# Philharmonic12.net
KiCad netlist of a schematic drawn in EAGLE
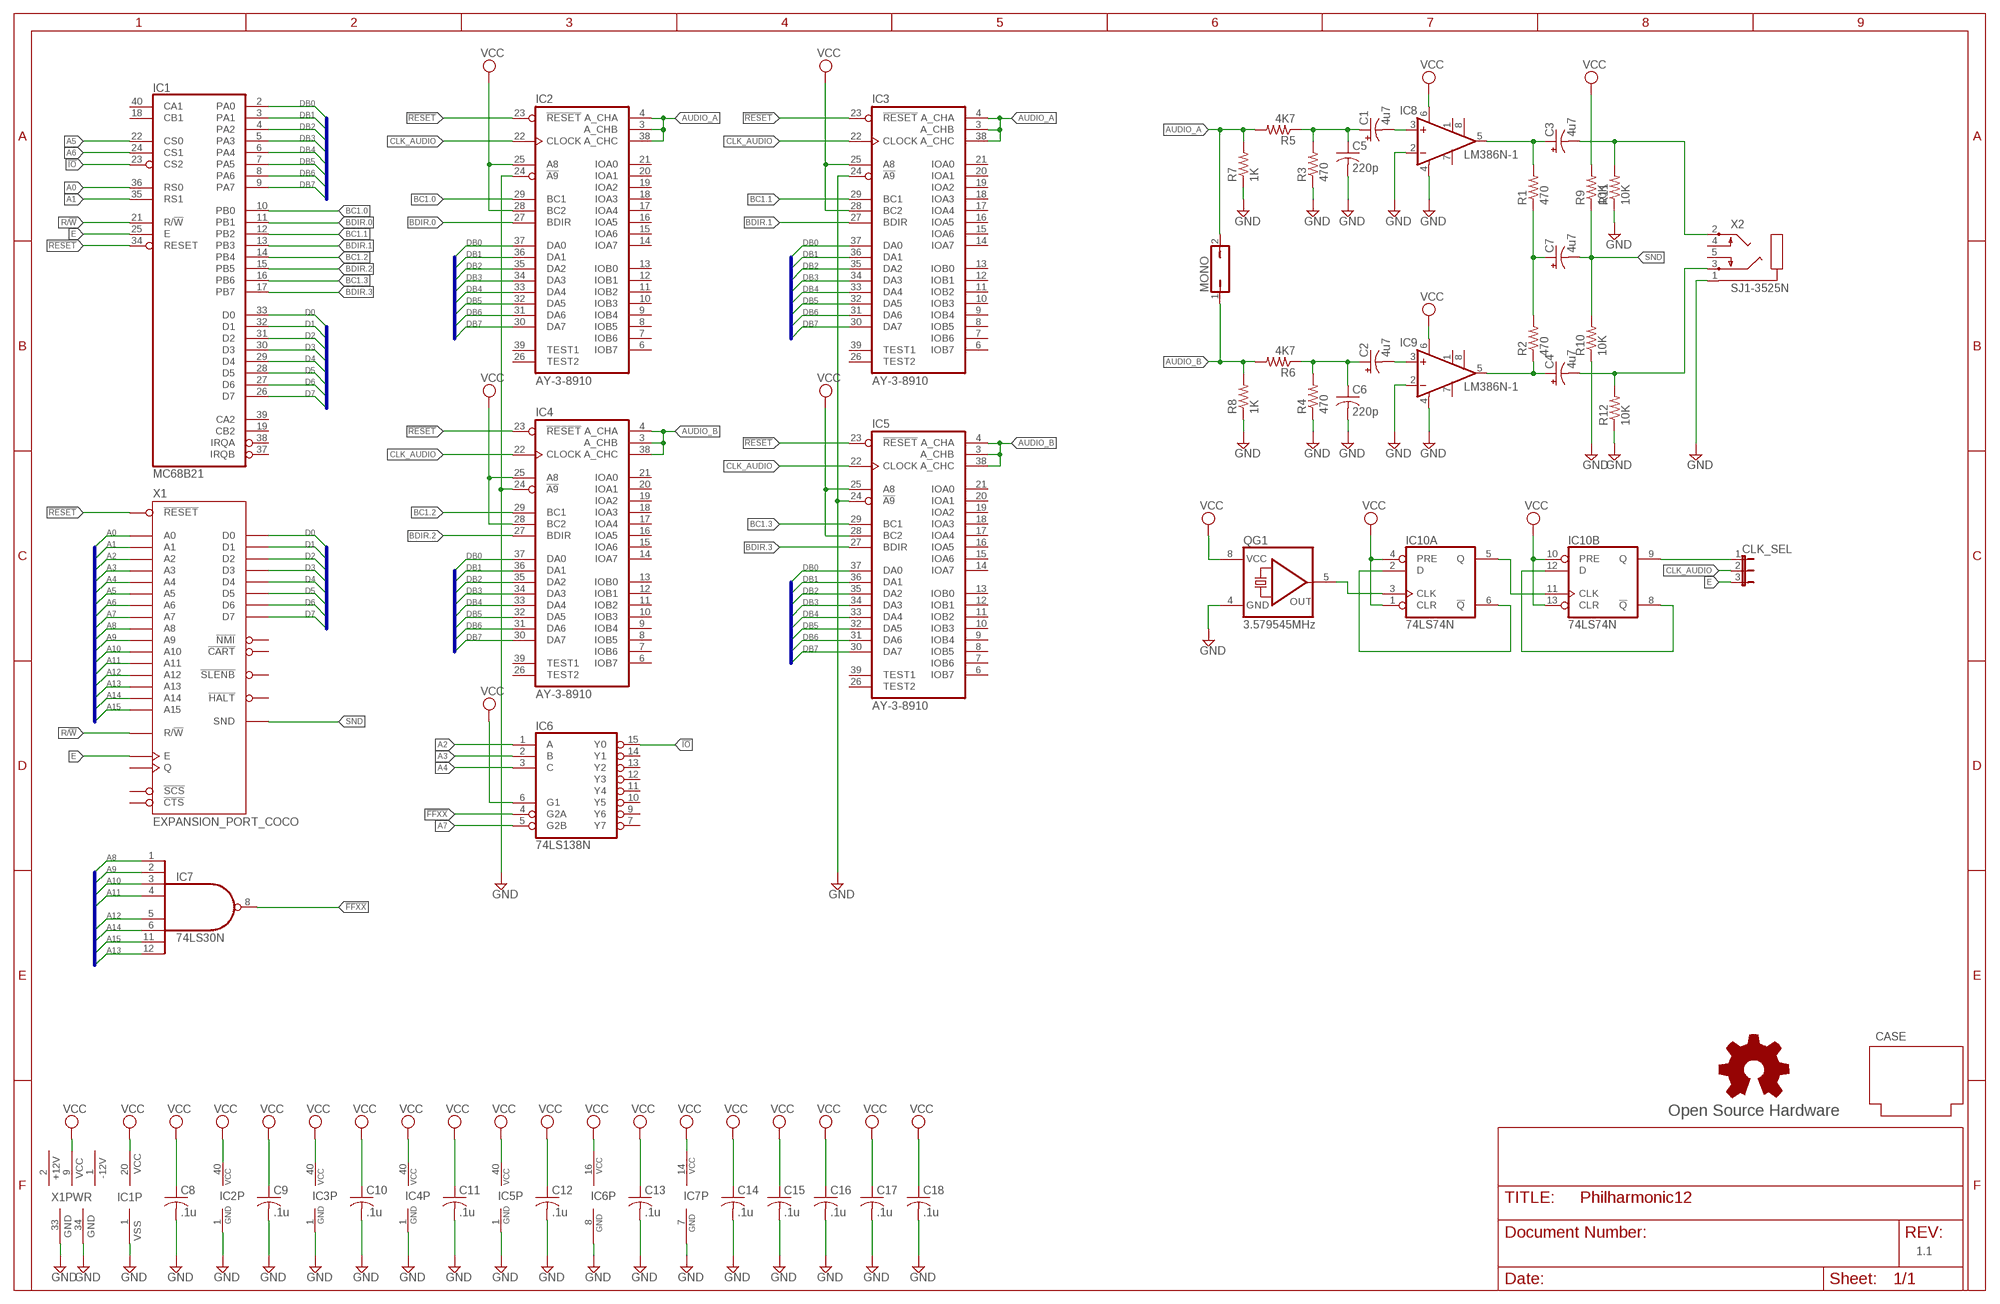
[diagram p0: schematic, sheet 1]

(export (version "E")
  (design (tool "Eeschema 10.0.6"))
  (components
    (comp (ref "C1")
      (value "4u7")
      (footprint "eagle-import:E2,5-6")
      (libsource (lib "eagle-import") (part "CPOL-USE2.5-6"))
    )
    (comp (ref "C2")
      (value "4u7")
      (footprint "eagle-import:E2,5-6")
      (libsource (lib "eagle-import") (part "CPOL-USE2.5-6"))
    )
    (comp (ref "C3")
      (value "4u7")
      (footprint "eagle-import:E2,5-6")
      (libsource (lib "eagle-import") (part "CPOL-USE2.5-6"))
    )
    (comp (ref "C4")
      (value "4u7")
      (footprint "eagle-import:E2,5-6")
      (libsource (lib "eagle-import") (part "CPOL-USE2.5-6"))
    )
    (comp (ref "C5")
      (value "220p")
      (footprint "eagle-import:C025-025X050")
      (libsource (lib "eagle-import") (part "C-US025-025X050"))
    )
    (comp (ref "C6")
      (value "220p")
      (footprint "eagle-import:C025-025X050")
      (libsource (lib "eagle-import") (part "C-US025-025X050"))
    )
    (comp (ref "C7")
      (value "4u7")
      (footprint "eagle-import:E2,5-6")
      (libsource (lib "eagle-import") (part "CPOL-USE2.5-6"))
    )
    (comp (ref "C8")
      (value ".1u")
      (footprint "eagle-import:C025-025X050")
      (libsource (lib "eagle-import") (part "C-US025-025X050"))
    )
    (comp (ref "C9")
      (value ".1u")
      (footprint "eagle-import:C025-025X050")
      (libsource (lib "eagle-import") (part "C-US025-025X050"))
    )
    (comp (ref "C10")
      (value ".1u")
      (footprint "eagle-import:C025-025X050")
      (libsource (lib "eagle-import") (part "C-US025-025X050"))
    )
    (comp (ref "C11")
      (value ".1u")
      (footprint "eagle-import:C025-025X050")
      (libsource (lib "eagle-import") (part "C-US025-025X050"))
    )
    (comp (ref "C12")
      (value ".1u")
      (footprint "eagle-import:C025-025X050")
      (libsource (lib "eagle-import") (part "C-US025-025X050"))
    )
    (comp (ref "C13")
      (value ".1u")
      (footprint "eagle-import:C025-025X050")
      (libsource (lib "eagle-import") (part "C-US025-025X050"))
    )
    (comp (ref "C14")
      (value ".1u")
      (footprint "eagle-import:C025-025X050")
      (libsource (lib "eagle-import") (part "C-US025-025X050"))
    )
    (comp (ref "C15")
      (value ".1u")
      (footprint "eagle-import:C025-025X050")
      (libsource (lib "eagle-import") (part "C-US025-025X050"))
    )
    (comp (ref "C16")
      (value ".1u")
      (footprint "eagle-import:C025-025X050")
      (libsource (lib "eagle-import") (part "C-US025-025X050"))
    )
    (comp (ref "C17")
      (value ".1u")
      (footprint "eagle-import:C025-025X050")
      (libsource (lib "eagle-import") (part "C-US025-025X050"))
    )
    (comp (ref "C18")
      (value ".1u")
      (footprint "eagle-import:C025-025X050")
      (libsource (lib "eagle-import") (part "C-US025-025X050"))
    )
    (comp (ref "CASE")
      (value "PROGRAM_PAK")
      (footprint "eagle-import:PROGRAM_PAK")
      (libsource (lib "eagle-import") (part "PROGRAM_PAK"))
    )
    (comp (ref "CLK_SEL")
      (value "JP2E")
      (footprint "eagle-import:JP2")
      (libsource (lib "eagle-import") (part "JP2E"))
    )
    (comp (ref "GOLD_ORB_SM1")
      (value "Open Source Hardware")
      (footprint "eagle-import:OSHW_5MM")
      (libsource (lib "eagle-import") (part "OSHWLOGOLOGO5MM"))
    )
    (comp (ref "IC1")
      (value "MC68B21")
      (footprint "eagle-import:DIL40-ROUNDPAD")
      (libsource (lib "eagle-import") (part "6821R"))
    )
    (comp (ref "IC2")
      (value "AY-3-8910")
      (footprint "eagle-import:DIL40-RP")
      (libsource (lib "eagle-import") (part "AY-3-8910-RP"))
    )
    (comp (ref "IC3")
      (value "AY-3-8910")
      (footprint "eagle-import:DIL40-RP")
      (libsource (lib "eagle-import") (part "AY-3-8910-RP"))
    )
    (comp (ref "IC4")
      (value "AY-3-8910")
      (footprint "eagle-import:DIL40-RP")
      (libsource (lib "eagle-import") (part "AY-3-8910-RP"))
    )
    (comp (ref "IC5")
      (value "AY-3-8910")
      (footprint "eagle-import:DIL40-RP")
      (libsource (lib "eagle-import") (part "AY-3-8910-RP"))
    )
    (comp (ref "IC6")
      (value "74LS138N")
      (footprint "eagle-import:DIL16-RP")
      (libsource (lib "eagle-import") (part "74138NLS"))
    )
    (comp (ref "IC7")
      (value "74LS30N")
      (footprint "eagle-import:DIL14-RP")
      (libsource (lib "eagle-import") (part "7430NALS"))
    )
    (comp (ref "IC8")
      (value "LM386N-1")
      (footprint "eagle-import:DIL08")
      (libsource (lib "eagle-import") (part "LM386?-N1"))
    )
    (comp (ref "IC9")
      (value "LM386N-1")
      (footprint "eagle-import:DIL08")
      (libsource (lib "eagle-import") (part "LM386?-N1"))
    )
    (comp (ref "IC10")
      (value "74LS74N")
      (footprint "eagle-import:DIL14-RP")
      (libsource (lib "eagle-import") (part "7474NLS"))
    )
    (comp (ref "MONO")
      (value "JP1Q")
      (footprint "eagle-import:JP1")
      (libsource (lib "eagle-import") (part "JP1Q"))
    )
    (comp (ref "QG1")
      (value "3.579545MHz")
      (footprint "eagle-import:DIL08S")
      (libsource (lib "eagle-import") (part "QG5460"))
    )
    (comp (ref "R1")
      (value "470")
      (footprint "eagle-import:0204_7")
      (libsource (lib "eagle-import") (part "R-US_0204/7"))
    )
    (comp (ref "R2")
      (value "470")
      (footprint "eagle-import:0204_7")
      (libsource (lib "eagle-import") (part "R-US_0204/7"))
    )
    (comp (ref "R3")
      (value "470")
      (footprint "eagle-import:0204_7")
      (libsource (lib "eagle-import") (part "R-US_0204/7"))
    )
    (comp (ref "R4")
      (value "470")
      (footprint "eagle-import:0204_7")
      (libsource (lib "eagle-import") (part "R-US_0204/7"))
    )
    (comp (ref "R5")
      (value "4K7")
      (footprint "eagle-import:0204_7")
      (libsource (lib "eagle-import") (part "R-US_0204/7"))
    )
    (comp (ref "R6")
      (value "4K7")
      (footprint "eagle-import:0204_7")
      (libsource (lib "eagle-import") (part "R-US_0204/7"))
    )
    (comp (ref "R7")
      (value "1K")
      (footprint "eagle-import:0204_7")
      (libsource (lib "eagle-import") (part "R-US_0204/7"))
    )
    (comp (ref "R8")
      (value "1K")
      (footprint "eagle-import:0204_7")
      (libsource (lib "eagle-import") (part "R-US_0204/7"))
    )
    (comp (ref "R9")
      (value "10K")
      (footprint "eagle-import:0204_7")
      (libsource (lib "eagle-import") (part "R-US_0204/7"))
    )
    (comp (ref "R10")
      (value "10K")
      (footprint "eagle-import:0204_7")
      (libsource (lib "eagle-import") (part "R-US_0204/7"))
    )
    (comp (ref "R11")
      (value "10K")
      (footprint "eagle-import:0204_7")
      (libsource (lib "eagle-import") (part "R-US_0204/7"))
    )
    (comp (ref "R12")
      (value "10K")
      (footprint "eagle-import:0204_7")
      (libsource (lib "eagle-import") (part "R-US_0204/7"))
    )
    (comp (ref "X1")
      (value "EXPANSION_PORT_COCO")
      (footprint "eagle-import:MA20-2")
      (libsource (lib "eagle-import") (part "EXPANSION_PORT_COCO"))
    )
    (comp (ref "X2")
      (value "SJ1-3525N")
      (footprint "eagle-import:SJ1-3525N")
      (libsource (lib "eagle-import") (part "SJ1-3525N"))
    )
  )
  (nets
    (net (code "1") (name "/+12V") (class "Default")
      (node (ref "X1") (pin "2") (pinfunction "+12V_2") (pintype "power_in"))
    )
    (net (code "2") (name "/-12V") (class "Default")
      (node (ref "X1") (pin "1") (pinfunction "-12V_1") (pintype "power_in"))
    )
    (net (code "3") (name "/A8") (class "Default")
      (node (ref "IC7") (pin "1") (pinfunction "I0_1") (pintype "input"))
      (node (ref "X1") (pin "27") (pinfunction "A8_27") (pintype "output"))
    )
    (net (code "4") (name "/A9") (class "Default")
      (node (ref "IC7") (pin "2") (pinfunction "I1_2") (pintype "input"))
      (node (ref "X1") (pin "28") (pinfunction "A9_28") (pintype "output"))
    )
    (net (code "5") (name "/A10") (class "Default")
      (node (ref "IC7") (pin "3") (pinfunction "I2_3") (pintype "input"))
      (node (ref "X1") (pin "29") (pinfunction "A10_29") (pintype "output"))
    )
    (net (code "6") (name "/A11") (class "Default")
      (node (ref "IC7") (pin "4") (pinfunction "I3_4") (pintype "input"))
      (node (ref "X1") (pin "30") (pinfunction "A11_30") (pintype "output"))
    )
    (net (code "7") (name "/A12") (class "Default")
      (node (ref "IC7") (pin "5") (pinfunction "I4_5") (pintype "input"))
      (node (ref "X1") (pin "31") (pinfunction "A12_31") (pintype "output"))
    )
    (net (code "8") (name "/A13") (class "Default")
      (node (ref "IC7") (pin "12") (pinfunction "I7_12") (pintype "input"))
      (node (ref "X1") (pin "37") (pinfunction "A13_37") (pintype "output"))
    )
    (net (code "9") (name "/A14") (class "Default")
      (node (ref "IC7") (pin "6") (pinfunction "I5_6") (pintype "input"))
      (node (ref "X1") (pin "38") (pinfunction "A14_38") (pintype "output"))
    )
    (net (code "10") (name "/A15") (class "Default")
      (node (ref "IC7") (pin "11") (pinfunction "I6_11") (pintype "input"))
      (node (ref "X1") (pin "39") (pinfunction "A15_39") (pintype "output"))
    )
    (net (code "11") (name "/D0") (class "Default")
      (node (ref "IC1") (pin "33") (pinfunction "D0_33") (pintype "bidirectional"))
      (node (ref "X1") (pin "10") (pinfunction "D0_10") (pintype "bidirectional"))
    )
    (net (code "12") (name "/D1") (class "Default")
      (node (ref "IC1") (pin "32") (pinfunction "D1_32") (pintype "bidirectional"))
      (node (ref "X1") (pin "11") (pinfunction "D1_11") (pintype "bidirectional"))
    )
    (net (code "13") (name "/D2") (class "Default")
      (node (ref "IC1") (pin "31") (pinfunction "D2_31") (pintype "bidirectional"))
      (node (ref "X1") (pin "12") (pinfunction "D2_12") (pintype "bidirectional"))
    )
    (net (code "14") (name "/D3") (class "Default")
      (node (ref "IC1") (pin "30") (pinfunction "D3_30") (pintype "bidirectional"))
      (node (ref "X1") (pin "13") (pinfunction "D3_13") (pintype "bidirectional"))
    )
    (net (code "15") (name "/D4") (class "Default")
      (node (ref "IC1") (pin "29") (pinfunction "D4_29") (pintype "bidirectional"))
      (node (ref "X1") (pin "14") (pinfunction "D4_14") (pintype "bidirectional"))
    )
    (net (code "16") (name "/D5") (class "Default")
      (node (ref "IC1") (pin "28") (pinfunction "D5_28") (pintype "bidirectional"))
      (node (ref "X1") (pin "15") (pinfunction "D5_15") (pintype "bidirectional"))
    )
    (net (code "17") (name "/D6") (class "Default")
      (node (ref "IC1") (pin "27") (pinfunction "D6_27") (pintype "bidirectional"))
      (node (ref "X1") (pin "16") (pinfunction "D6_16") (pintype "bidirectional"))
    )
    (net (code "18") (name "/D7") (class "Default")
      (node (ref "IC1") (pin "26") (pinfunction "D7_26") (pintype "bidirectional"))
      (node (ref "X1") (pin "17") (pinfunction "D7_17") (pintype "bidirectional"))
    )
    (net (code "19") (name "/DB0") (class "Default")
      (node (ref "IC1") (pin "2") (pinfunction "PA0_2") (pintype "bidirectional"))
      (node (ref "IC2") (pin "37") (pinfunction "DA0_37") (pintype "bidirectional"))
      (node (ref "IC3") (pin "37") (pinfunction "DA0_37") (pintype "bidirectional"))
      (node (ref "IC4") (pin "37") (pinfunction "DA0_37") (pintype "bidirectional"))
      (node (ref "IC5") (pin "37") (pinfunction "DA0_37") (pintype "bidirectional"))
    )
    (net (code "20") (name "/DB1") (class "Default")
      (node (ref "IC1") (pin "3") (pinfunction "PA1_3") (pintype "bidirectional"))
      (node (ref "IC2") (pin "36") (pinfunction "DA1_36") (pintype "bidirectional"))
      (node (ref "IC3") (pin "36") (pinfunction "DA1_36") (pintype "bidirectional"))
      (node (ref "IC4") (pin "36") (pinfunction "DA1_36") (pintype "bidirectional"))
      (node (ref "IC5") (pin "36") (pinfunction "DA1_36") (pintype "bidirectional"))
    )
    (net (code "21") (name "/DB2") (class "Default")
      (node (ref "IC1") (pin "4") (pinfunction "PA2_4") (pintype "bidirectional"))
      (node (ref "IC2") (pin "35") (pinfunction "DA2_35") (pintype "bidirectional"))
      (node (ref "IC3") (pin "35") (pinfunction "DA2_35") (pintype "bidirectional"))
      (node (ref "IC4") (pin "35") (pinfunction "DA2_35") (pintype "bidirectional"))
      (node (ref "IC5") (pin "35") (pinfunction "DA2_35") (pintype "bidirectional"))
    )
    (net (code "22") (name "/DB3") (class "Default")
      (node (ref "IC1") (pin "5") (pinfunction "PA3_5") (pintype "bidirectional"))
      (node (ref "IC2") (pin "34") (pinfunction "DA3_34") (pintype "bidirectional"))
      (node (ref "IC3") (pin "34") (pinfunction "DA3_34") (pintype "bidirectional"))
      (node (ref "IC4") (pin "34") (pinfunction "DA3_34") (pintype "bidirectional"))
      (node (ref "IC5") (pin "34") (pinfunction "DA3_34") (pintype "bidirectional"))
    )
    (net (code "23") (name "/DB4") (class "Default")
      (node (ref "IC1") (pin "6") (pinfunction "PA4_6") (pintype "bidirectional"))
      (node (ref "IC2") (pin "33") (pinfunction "DA4_33") (pintype "bidirectional"))
      (node (ref "IC3") (pin "33") (pinfunction "DA4_33") (pintype "bidirectional"))
      (node (ref "IC4") (pin "33") (pinfunction "DA4_33") (pintype "bidirectional"))
      (node (ref "IC5") (pin "33") (pinfunction "DA4_33") (pintype "bidirectional"))
    )
    (net (code "24") (name "/DB5") (class "Default")
      (node (ref "IC1") (pin "7") (pinfunction "PA5_7") (pintype "bidirectional"))
      (node (ref "IC2") (pin "32") (pinfunction "DA5_32") (pintype "bidirectional"))
      (node (ref "IC3") (pin "32") (pinfunction "DA5_32") (pintype "bidirectional"))
      (node (ref "IC4") (pin "32") (pinfunction "DA5_32") (pintype "bidirectional"))
      (node (ref "IC5") (pin "32") (pinfunction "DA5_32") (pintype "bidirectional"))
    )
    (net (code "25") (name "/DB6") (class "Default")
      (node (ref "IC1") (pin "8") (pinfunction "PA6_8") (pintype "bidirectional"))
      (node (ref "IC2") (pin "31") (pinfunction "DA6_31") (pintype "bidirectional"))
      (node (ref "IC3") (pin "31") (pinfunction "DA6_31") (pintype "bidirectional"))
      (node (ref "IC4") (pin "31") (pinfunction "DA6_31") (pintype "bidirectional"))
      (node (ref "IC5") (pin "31") (pinfunction "DA6_31") (pintype "bidirectional"))
    )
    (net (code "26") (name "/DB7") (class "Default")
      (node (ref "IC1") (pin "9") (pinfunction "PA7_9") (pintype "bidirectional"))
      (node (ref "IC2") (pin "30") (pinfunction "DA7_30") (pintype "bidirectional"))
      (node (ref "IC3") (pin "30") (pinfunction "DA7_30") (pintype "bidirectional"))
      (node (ref "IC4") (pin "30") (pinfunction "DA7_30") (pintype "bidirectional"))
      (node (ref "IC5") (pin "30") (pinfunction "DA7_30") (pintype "bidirectional"))
    )
    (net (code "27") (name "/R{slash}~{W}") (class "Default")
      (node (ref "IC1") (pin "21") (pinfunction "R/~{W}_21") (pintype "input"))
      (node (ref "X1") (pin "18") (pinfunction "R/~{W}_18") (pintype "output"))
    )
    (net (code "28") (name "/~{FFXX}") (class "Default")
      (node (ref "IC6") (pin "4") (pinfunction "G2A_4") (pintype "input"))
      (node (ref "IC7") (pin "8") (pinfunction "O_8") (pintype "output"))
    )
    (net (code "29") (name "/~{IO}") (class "Default")
      (node (ref "IC1") (pin "23") (pinfunction "CS2_23") (pintype "input"))
      (node (ref "IC6") (pin "15") (pinfunction "Y0_15") (pintype "output"))
    )
    (net (code "30") (name "/~{RESET}") (class "Default")
      (node (ref "IC1") (pin "34") (pinfunction "RESET_34") (pintype "input"))
      (node (ref "IC2") (pin "23") (pinfunction "~{RESET}_23") (pintype "input"))
      (node (ref "IC3") (pin "23") (pinfunction "~{RESET}_23") (pintype "input"))
      (node (ref "IC4") (pin "23") (pinfunction "~{RESET}_23") (pintype "input"))
      (node (ref "IC5") (pin "23") (pinfunction "~{RESET}_23") (pintype "input"))
      (node (ref "X1") (pin "5") (pinfunction "~{RESET}_5") (pintype "open_collector"))
    )
    (net (code "31") (name "A0") (class "Default")
      (node (ref "IC1") (pin "36") (pinfunction "RS0_36") (pintype "input"))
      (node (ref "X1") (pin "19") (pinfunction "A0_19") (pintype "output"))
    )
    (net (code "32") (name "A1") (class "Default")
      (node (ref "IC1") (pin "35") (pinfunction "RS1_35") (pintype "input"))
      (node (ref "X1") (pin "20") (pinfunction "A1_20") (pintype "output"))
    )
    (net (code "33") (name "A2") (class "Default")
      (node (ref "IC6") (pin "1") (pinfunction "A_1") (pintype "input"))
      (node (ref "X1") (pin "21") (pinfunction "A2_21") (pintype "output"))
    )
    (net (code "34") (name "A3") (class "Default")
      (node (ref "IC6") (pin "2") (pinfunction "B_2") (pintype "input"))
      (node (ref "X1") (pin "22") (pinfunction "A3_22") (pintype "output"))
    )
    (net (code "35") (name "A4") (class "Default")
      (node (ref "IC6") (pin "3") (pinfunction "C_3") (pintype "input"))
      (node (ref "X1") (pin "23") (pinfunction "A4_23") (pintype "output"))
    )
    (net (code "36") (name "A5") (class "Default")
      (node (ref "IC1") (pin "22") (pinfunction "CS0_22") (pintype "input"))
      (node (ref "X1") (pin "24") (pinfunction "A5_24") (pintype "output"))
    )
    (net (code "37") (name "A6") (class "Default")
      (node (ref "IC1") (pin "24") (pinfunction "CS1_24") (pintype "input"))
      (node (ref "X1") (pin "25") (pinfunction "A6_25") (pintype "output"))
    )
    (net (code "38") (name "A7") (class "Default")
      (node (ref "IC6") (pin "5") (pinfunction "G2B_5") (pintype "input"))
      (node (ref "X1") (pin "26") (pinfunction "A7_26") (pintype "output"))
    )
    (net (code "39") (name "AUDIO_A") (class "Default")
      (node (ref "IC2") (pin "3") (pinfunction "A_CHB_3") (pintype "output"))
      (node (ref "IC2") (pin "38") (pinfunction "A_CHC_38") (pintype "output"))
      (node (ref "IC2") (pin "4") (pinfunction "A_CHA_4") (pintype "output"))
      (node (ref "IC3") (pin "3") (pinfunction "A_CHB_3") (pintype "output"))
      (node (ref "IC3") (pin "38") (pinfunction "A_CHC_38") (pintype "output"))
      (node (ref "IC3") (pin "4") (pinfunction "A_CHA_4") (pintype "output"))
      (node (ref "MONO") (pin "2") (pinfunction "2_2") (pintype "passive"))
      (node (ref "R5") (pin "2") (pinfunction "2_2") (pintype "passive"))
      (node (ref "R7") (pin "2") (pinfunction "2_2") (pintype "passive"))
    )
    (net (code "40") (name "AUDIO_B") (class "Default")
      (node (ref "IC4") (pin "3") (pinfunction "A_CHB_3") (pintype "output"))
      (node (ref "IC4") (pin "38") (pinfunction "A_CHC_38") (pintype "output"))
      (node (ref "IC4") (pin "4") (pinfunction "A_CHA_4") (pintype "output"))
      (node (ref "IC5") (pin "3") (pinfunction "A_CHB_3") (pintype "output"))
      (node (ref "IC5") (pin "38") (pinfunction "A_CHC_38") (pintype "output"))
      (node (ref "IC5") (pin "4") (pinfunction "A_CHA_4") (pintype "output"))
      (node (ref "MONO") (pin "1") (pinfunction "1_1") (pintype "passive"))
      (node (ref "R6") (pin "2") (pinfunction "2_2") (pintype "passive"))
      (node (ref "R8") (pin "2") (pinfunction "2_2") (pintype "passive"))
    )
    (net (code "41") (name "BC1.0") (class "Default")
      (node (ref "IC1") (pin "10") (pinfunction "PB0_10") (pintype "bidirectional"))
      (node (ref "IC2") (pin "29") (pinfunction "BC1_29") (pintype "input"))
    )
    (net (code "42") (name "BC1.1") (class "Default")
      (node (ref "IC1") (pin "12") (pinfunction "PB2_12") (pintype "bidirectional"))
      (node (ref "IC3") (pin "29") (pinfunction "BC1_29") (pintype "input"))
    )
    (net (code "43") (name "BC1.2") (class "Default")
      (node (ref "IC1") (pin "14") (pinfunction "PB4_14") (pintype "bidirectional"))
      (node (ref "IC4") (pin "29") (pinfunction "BC1_29") (pintype "input"))
    )
    (net (code "44") (name "BC1.3") (class "Default")
      (node (ref "IC1") (pin "16") (pinfunction "PB6_16") (pintype "bidirectional"))
      (node (ref "IC5") (pin "29") (pinfunction "BC1_29") (pintype "input"))
    )
    (net (code "45") (name "BDIR.0") (class "Default")
      (node (ref "IC1") (pin "11") (pinfunction "PB1_11") (pintype "bidirectional"))
      (node (ref "IC2") (pin "27") (pinfunction "BDIR_27") (pintype "input"))
    )
    (net (code "46") (name "BDIR.1") (class "Default")
      (node (ref "IC1") (pin "13") (pinfunction "PB3_13") (pintype "bidirectional"))
      (node (ref "IC3") (pin "27") (pinfunction "BDIR_27") (pintype "input"))
    )
    (net (code "47") (name "BDIR.2") (class "Default")
      (node (ref "IC1") (pin "15") (pinfunction "PB5_15") (pintype "bidirectional"))
      (node (ref "IC4") (pin "27") (pinfunction "BDIR_27") (pintype "input"))
    )
    (net (code "48") (name "BDIR.3") (class "Default")
      (node (ref "IC1") (pin "17") (pinfunction "PB7_17") (pintype "bidirectional"))
      (node (ref "IC5") (pin "27") (pinfunction "BDIR_27") (pintype "input"))
    )
    (net (code "49") (name "CLK_AUDIO") (class "Default")
      (node (ref "CLK_SEL") (pin "2") (pinfunction "2_2") (pintype "passive"))
      (node (ref "IC2") (pin "22") (pinfunction "CLOCK_22") (pintype "input"))
      (node (ref "IC3") (pin "22") (pinfunction "CLOCK_22") (pintype "input"))
      (node (ref "IC4") (pin "22") (pinfunction "CLOCK_22") (pintype "input"))
      (node (ref "IC5") (pin "22") (pinfunction "CLOCK_22") (pintype "input"))
    )
    (net (code "50") (name "E") (class "Default")
      (node (ref "CLK_SEL") (pin "3") (pinfunction "3_3") (pintype "passive"))
      (node (ref "IC1") (pin "25") (pinfunction "E_25") (pintype "input"))
      (node (ref "X1") (pin "6") (pinfunction "E_6") (pintype "output"))
    )
    (net (code "51") (name "GND") (class "Default")
      (node (ref "C10") (pin "2") (pinfunction "2_2") (pintype "passive"))
      (node (ref "C11") (pin "2") (pinfunction "2_2") (pintype "passive"))
      (node (ref "C12") (pin "2") (pinfunction "2_2") (pintype "passive"))
      (node (ref "C13") (pin "2") (pinfunction "2_2") (pintype "passive"))
      (node (ref "C14") (pin "2") (pinfunction "2_2") (pintype "passive"))
      (node (ref "C15") (pin "2") (pinfunction "2_2") (pintype "passive"))
      (node (ref "C16") (pin "2") (pinfunction "2_2") (pintype "passive"))
      (node (ref "C17") (pin "2") (pinfunction "2_2") (pintype "passive"))
      (node (ref "C18") (pin "2") (pinfunction "2_2") (pintype "passive"))
      (node (ref "C5") (pin "2") (pinfunction "2_2") (pintype "passive"))
      (node (ref "C6") (pin "2") (pinfunction "2_2") (pintype "passive"))
      (node (ref "C8") (pin "2") (pinfunction "2_2") (pintype "passive"))
      (node (ref "C9") (pin "2") (pinfunction "2_2") (pintype "passive"))
      (node (ref "IC1") (pin "1") (pinfunction "VSS_1") (pintype "power_in"))
      (node (ref "IC2") (pin "1") (pinfunction "GND_1") (pintype "power_in"))
      (node (ref "IC2") (pin "24") (pinfunction "~{A9}_24") (pintype "input"))
      (node (ref "IC3") (pin "1") (pinfunction "GND_1") (pintype "power_in"))
      (node (ref "IC3") (pin "24") (pinfunction "~{A9}_24") (pintype "input"))
      (node (ref "IC4") (pin "1") (pinfunction "GND_1") (pintype "power_in"))
      (node (ref "IC4") (pin "24") (pinfunction "~{A9}_24") (pintype "input"))
      (node (ref "IC5") (pin "1") (pinfunction "GND_1") (pintype "power_in"))
      (node (ref "IC5") (pin "24") (pinfunction "~{A9}_24") (pintype "input"))
      (node (ref "IC6") (pin "8") (pinfunction "GND_8") (pintype "power_in"))
      (node (ref "IC7") (pin "7") (pinfunction "GND_7") (pintype "power_in"))
      (node (ref "IC8") (pin "2") (pinfunction "-IN_2") (pintype "input"))
      (node (ref "IC8") (pin "4") (pinfunction "GND_4") (pintype "power_in"))
      (node (ref "IC9") (pin "2") (pinfunction "-IN_2") (pintype "input"))
      (node (ref "IC9") (pin "4") (pinfunction "GND_4") (pintype "power_in"))
      (node (ref "QG1") (pin "4") (pinfunction "GND_4") (pintype "power_in"))
      (node (ref "R10") (pin "1") (pinfunction "1_1") (pintype "passive"))
      (node (ref "R11") (pin "1") (pinfunction "1_1") (pintype "passive"))
      (node (ref "R12") (pin "1") (pinfunction "1_1") (pintype "passive"))
      (node (ref "R3") (pin "1") (pinfunction "1_1") (pintype "passive"))
      (node (ref "R4") (pin "1") (pinfunction "1_1") (pintype "passive"))
      (node (ref "R7") (pin "1") (pinfunction "1_1") (pintype "passive"))
      (node (ref "R8") (pin "1") (pinfunction "1_1") (pintype "passive"))
      (node (ref "X1") (pin "33") (pinfunction "GND_33") (pintype "power_in"))
      (node (ref "X1") (pin "34") (pinfunction "GND_34") (pintype "power_in"))
      (node (ref "X2") (pin "1") (pinfunction "1_1") (pintype "passive"))
    )
    (net (code "52") (name "Net-(C1-Pad+)") (class "Default")
      (node (ref "C1") (pin "+") (pinfunction "+_+") (pintype "passive"))
      (node (ref "C5") (pin "1") (pinfunction "1_1") (pintype "passive"))
      (node (ref "R3") (pin "2") (pinfunction "2_2") (pintype "passive"))
      (node (ref "R5") (pin "1") (pinfunction "1_1") (pintype "passive"))
    )
    (net (code "53") (name "Net-(C2-Pad+)") (class "Default")
      (node (ref "C2") (pin "+") (pinfunction "+_+") (pintype "passive"))
      (node (ref "C6") (pin "1") (pinfunction "1_1") (pintype "passive"))
      (node (ref "R4") (pin "2") (pinfunction "2_2") (pintype "passive"))
      (node (ref "R6") (pin "1") (pinfunction "1_1") (pintype "passive"))
    )
    (net (code "54") (name "Net-(C3-Pad-)") (class "Default")
      (node (ref "C3") (pin "-") (pinfunction "-_-") (pintype "passive"))
      (node (ref "R11") (pin "2") (pinfunction "2_2") (pintype "passive"))
      (node (ref "X2") (pin "2") (pinfunction "2_2") (pintype "passive"))
    )
    (net (code "55") (name "Net-(C4-Pad-)") (class "Default")
      (node (ref "C4") (pin "-") (pinfunction "-_-") (pintype "passive"))
      (node (ref "R12") (pin "2") (pinfunction "2_2") (pintype "passive"))
      (node (ref "X2") (pin "3") (pinfunction "3_3") (pintype "passive"))
    )
    (net (code "56") (name "Net-(C7-Pad+)") (class "Default")
      (node (ref "C7") (pin "+") (pinfunction "+_+") (pintype "passive"))
      (node (ref "R1") (pin "1") (pinfunction "1_1") (pintype "passive"))
      (node (ref "R2") (pin "2") (pinfunction "2_2") (pintype "passive"))
    )
    (net (code "57") (name "Net-(IC8-+IN)") (class "Default")
      (node (ref "C1") (pin "-") (pinfunction "-_-") (pintype "passive"))
      (node (ref "IC8") (pin "3") (pinfunction "+IN_3") (pintype "input"))
    )
    (net (code "58") (name "Net-(IC8-OUT)") (class "Default")
      (node (ref "C3") (pin "+") (pinfunction "+_+") (pintype "passive"))
      (node (ref "IC8") (pin "5") (pinfunction "OUT_5") (pintype "output"))
      (node (ref "R1") (pin "2") (pinfunction "2_2") (pintype "passive"))
    )
    (net (code "59") (name "Net-(IC9-+IN)") (class "Default")
      (node (ref "C2") (pin "-") (pinfunction "-_-") (pintype "passive"))
      (node (ref "IC9") (pin "3") (pinfunction "+IN_3") (pintype "input"))
    )
    (net (code "60") (name "Net-(IC9-OUT)") (class "Default")
      (node (ref "C4") (pin "+") (pinfunction "+_+") (pintype "passive"))
      (node (ref "IC9") (pin "5") (pinfunction "OUT_5") (pintype "output"))
      (node (ref "R2") (pin "1") (pinfunction "1_1") (pintype "passive"))
    )
    (net (code "61") (name "Net-(IC10A-CLK)") (class "Default")
      (node (ref "IC10") (pin "3") (pinfunction "CLK_3") (pintype "input"))
      (node (ref "QG1") (pin "5") (pinfunction "OUT_5") (pintype "output"))
    )
    (net (code "62") (name "Net-(IC10A-D)") (class "Default")
      (node (ref "IC10") (pin "2") (pinfunction "D_2") (pintype "input"))
      (node (ref "IC10") (pin "6") (pinfunction "~{Q}_6") (pintype "output"))
    )
    (net (code "63") (name "Net-(IC10A-Q)") (class "Default")
      (node (ref "IC10") (pin "11") (pinfunction "CLK_11") (pintype "input"))
      (node (ref "IC10") (pin "5") (pinfunction "Q_5") (pintype "output"))
    )
    (net (code "64") (name "Net-(IC10B-D)") (class "Default")
      (node (ref "IC10") (pin "12") (pinfunction "D_12") (pintype "input"))
      (node (ref "IC10") (pin "8") (pinfunction "~{Q}_8") (pintype "output"))
    )
    (net (code "65") (name "Net-(IC10B-Q)") (class "Default")
      (node (ref "CLK_SEL") (pin "1") (pinfunction "1_1") (pintype "passive"))
      (node (ref "IC10") (pin "9") (pinfunction "Q_9") (pintype "output"))
    )
    (net (code "66") (name "SND") (class "Default")
      (node (ref "C7") (pin "-") (pinfunction "-_-") (pintype "passive"))
      (node (ref "R10") (pin "2") (pinfunction "2_2") (pintype "passive"))
      (node (ref "R9") (pin "1") (pinfunction "1_1") (pintype "passive"))
      (node (ref "X1") (pin "35") (pinfunction "SND_35") (pintype "passive"))
    )
    (net (code "67") (name "VCC") (class "Default")
      (node (ref "C10") (pin "1") (pinfunction "1_1") (pintype "passive"))
      (node (ref "C11") (pin "1") (pinfunction "1_1") (pintype "passive"))
      (node (ref "C12") (pin "1") (pinfunction "1_1") (pintype "passive"))
      (node (ref "C13") (pin "1") (pinfunction "1_1") (pintype "passive"))
      (node (ref "C14") (pin "1") (pinfunction "1_1") (pintype "passive"))
      (node (ref "C15") (pin "1") (pinfunction "1_1") (pintype "passive"))
      (node (ref "C16") (pin "1") (pinfunction "1_1") (pintype "passive"))
      (node (ref "C17") (pin "1") (pinfunction "1_1") (pintype "passive"))
      (node (ref "C18") (pin "1") (pinfunction "1_1") (pintype "passive"))
      (node (ref "C8") (pin "1") (pinfunction "1_1") (pintype "passive"))
      (node (ref "C9") (pin "1") (pinfunction "1_1") (pintype "passive"))
      (node (ref "IC1") (pin "20") (pinfunction "VCC_20") (pintype "power_in"))
      (node (ref "IC10") (pin "1") (pinfunction "CLR_1") (pintype "input"))
      (node (ref "IC10") (pin "10") (pinfunction "PRE_10") (pintype "input"))
      (node (ref "IC10") (pin "13") (pinfunction "CLR_13") (pintype "input"))
      (node (ref "IC10") (pin "4") (pinfunction "PRE_4") (pintype "input"))
      (node (ref "IC2") (pin "25") (pinfunction "A8_25") (pintype "input"))
      (node (ref "IC2") (pin "28") (pinfunction "BC2_28") (pintype "input"))
      (node (ref "IC2") (pin "40") (pinfunction "VCC_40") (pintype "power_in"))
      (node (ref "IC3") (pin "25") (pinfunction "A8_25") (pintype "input"))
      (node (ref "IC3") (pin "28") (pinfunction "BC2_28") (pintype "input"))
      (node (ref "IC3") (pin "40") (pinfunction "VCC_40") (pintype "power_in"))
      (node (ref "IC4") (pin "25") (pinfunction "A8_25") (pintype "input"))
      (node (ref "IC4") (pin "28") (pinfunction "BC2_28") (pintype "input"))
      (node (ref "IC4") (pin "40") (pinfunction "VCC_40") (pintype "power_in"))
      (node (ref "IC5") (pin "25") (pinfunction "A8_25") (pintype "input"))
      (node (ref "IC5") (pin "28") (pinfunction "BC2_28") (pintype "input"))
      (node (ref "IC5") (pin "40") (pinfunction "VCC_40") (pintype "power_in"))
      (node (ref "IC6") (pin "16") (pinfunction "VCC_16") (pintype "power_in"))
      (node (ref "IC6") (pin "6") (pinfunction "G1_6") (pintype "input"))
      (node (ref "IC7") (pin "14") (pinfunction "VCC_14") (pintype "power_in"))
      (node (ref "IC8") (pin "6") (pinfunction "VS_6") (pintype "power_in"))
      (node (ref "IC9") (pin "6") (pinfunction "VS_6") (pintype "power_in"))
      (node (ref "QG1") (pin "8") (pinfunction "VCC_8") (pintype "power_in"))
      (node (ref "R9") (pin "2") (pinfunction "2_2") (pintype "passive"))
      (node (ref "X1") (pin "9") (pinfunction "VCC_9") (pintype "power_in"))
    )
    (net (code "68") (name "unconnected-(IC1A-CA1-Pad40)") (class "Default")
      (node (ref "IC1") (pin "40") (pinfunction "CA1_40") (pintype "input"))
    )
    (net (code "69") (name "unconnected-(IC1A-CA2-Pad39)") (class "Default")
      (node (ref "IC1") (pin "39") (pinfunction "CA2_39") (pintype "bidirectional"))
    )
    (net (code "70") (name "unconnected-(IC1A-CB1-Pad18)") (class "Default")
      (node (ref "IC1") (pin "18") (pinfunction "CB1_18") (pintype "input"))
    )
    (net (code "71") (name "unconnected-(IC1A-CB2-Pad19)") (class "Default")
      (node (ref "IC1") (pin "19") (pinfunction "CB2_19") (pintype "bidirectional"))
    )
    (net (code "72") (name "unconnected-(IC1A-IRQA-Pad38)") (class "Default")
      (node (ref "IC1") (pin "38") (pinfunction "IRQA_38") (pintype "open_collector"))
    )
    (net (code "73") (name "unconnected-(IC1A-IRQB-Pad37)") (class "Default")
      (node (ref "IC1") (pin "37") (pinfunction "IRQB_37") (pintype "open_collector"))
    )
    (net (code "74") (name "unconnected-(IC2A-IOA0-Pad21)") (class "Default")
      (node (ref "IC2") (pin "21") (pinfunction "IOA0_21") (pintype "bidirectional"))
    )
    (net (code "75") (name "unconnected-(IC2A-IOA1-Pad20)") (class "Default")
      (node (ref "IC2") (pin "20") (pinfunction "IOA1_20") (pintype "bidirectional"))
    )
    (net (code "76") (name "unconnected-(IC2A-IOA2-Pad19)") (class "Default")
      (node (ref "IC2") (pin "19") (pinfunction "IOA2_19") (pintype "bidirectional"))
    )
    (net (code "77") (name "unconnected-(IC2A-IOA3-Pad18)") (class "Default")
      (node (ref "IC2") (pin "18") (pinfunction "IOA3_18") (pintype "bidirectional"))
    )
    (net (code "78") (name "unconnected-(IC2A-IOA4-Pad17)") (class "Default")
      (node (ref "IC2") (pin "17") (pinfunction "IOA4_17") (pintype "bidirectional"))
    )
    (net (code "79") (name "unconnected-(IC2A-IOA5-Pad16)") (class "Default")
      (node (ref "IC2") (pin "16") (pinfunction "IOA5_16") (pintype "bidirectional"))
    )
    (net (code "80") (name "unconnected-(IC2A-IOA6-Pad15)") (class "Default")
      (node (ref "IC2") (pin "15") (pinfunction "IOA6_15") (pintype "bidirectional"))
    )
    (net (code "81") (name "unconnected-(IC2A-IOA7-Pad14)") (class "Default")
      (node (ref "IC2") (pin "14") (pinfunction "IOA7_14") (pintype "bidirectional"))
    )
    (net (code "82") (name "unconnected-(IC2A-IOB0-Pad13)") (class "Default")
      (node (ref "IC2") (pin "13") (pinfunction "IOB0_13") (pintype "bidirectional"))
    )
    (net (code "83") (name "unconnected-(IC2A-IOB1-Pad12)") (class "Default")
      (node (ref "IC2") (pin "12") (pinfunction "IOB1_12") (pintype "bidirectional"))
    )
    (net (code "84") (name "unconnected-(IC2A-IOB2-Pad11)") (class "Default")
      (node (ref "IC2") (pin "11") (pinfunction "IOB2_11") (pintype "bidirectional"))
    )
    (net (code "85") (name "unconnected-(IC2A-IOB3-Pad10)") (class "Default")
      (node (ref "IC2") (pin "10") (pinfunction "IOB3_10") (pintype "bidirectional"))
    )
    (net (code "86") (name "unconnected-(IC2A-IOB4-Pad9)") (class "Default")
      (node (ref "IC2") (pin "9") (pinfunction "IOB4_9") (pintype "bidirectional"))
    )
    (net (code "87") (name "unconnected-(IC2A-IOB5-Pad8)") (class "Default")
      (node (ref "IC2") (pin "8") (pinfunction "IOB5_8") (pintype "bidirectional"))
    )
    (net (code "88") (name "unconnected-(IC2A-IOB6-Pad7)") (class "Default")
      (node (ref "IC2") (pin "7") (pinfunction "IOB6_7") (pintype "bidirectional"))
    )
    (net (code "89") (name "unconnected-(IC2A-IOB7-Pad6)") (class "Default")
      (node (ref "IC2") (pin "6") (pinfunction "IOB7_6") (pintype "bidirectional"))
    )
    (net (code "90") (name "unconnected-(IC2A-TEST1-Pad39)") (class "Default")
      (node (ref "IC2") (pin "39") (pinfunction "TEST1_39") (pintype "input"))
    )
    (net (code "91") (name "unconnected-(IC2A-TEST2-Pad26)") (class "Default")
      (node (ref "IC2") (pin "26") (pinfunction "TEST2_26") (pintype "input"))
    )
    (net (code "92") (name "unconnected-(IC3A-IOA0-Pad21)") (class "Default")
      (node (ref "IC3") (pin "21") (pinfunction "IOA0_21") (pintype "bidirectional"))
    )
    (net (code "93") (name "unconnected-(IC3A-IOA1-Pad20)") (class "Default")
      (node (ref "IC3") (pin "20") (pinfunction "IOA1_20") (pintype "bidirectional"))
    )
    (net (code "94") (name "unconnected-(IC3A-IOA2-Pad19)") (class "Default")
      (node (ref "IC3") (pin "19") (pinfunction "IOA2_19") (pintype "bidirectional"))
    )
    (net (code "95") (name "unconnected-(IC3A-IOA3-Pad18)") (class "Default")
      (node (ref "IC3") (pin "18") (pinfunction "IOA3_18") (pintype "bidirectional"))
    )
    (net (code "96") (name "unconnected-(IC3A-IOA4-Pad17)") (class "Default")
      (node (ref "IC3") (pin "17") (pinfunction "IOA4_17") (pintype "bidirectional"))
    )
    (net (code "97") (name "unconnected-(IC3A-IOA5-Pad16)") (class "Default")
      (node (ref "IC3") (pin "16") (pinfunction "IOA5_16") (pintype "bidirectional"))
    )
    (net (code "98") (name "unconnected-(IC3A-IOA6-Pad15)") (class "Default")
      (node (ref "IC3") (pin "15") (pinfunction "IOA6_15") (pintype "bidirectional"))
    )
    (net (code "99") (name "unconnected-(IC3A-IOA7-Pad14)") (class "Default")
      (node (ref "IC3") (pin "14") (pinfunction "IOA7_14") (pintype "bidirectional"))
    )
    (net (code "100") (name "unconnected-(IC3A-IOB0-Pad13)") (class "Default")
      (node (ref "IC3") (pin "13") (pinfunction "IOB0_13") (pintype "bidirectional"))
    )
    (net (code "101") (name "unconnected-(IC3A-IOB1-Pad12)") (class "Default")
      (node (ref "IC3") (pin "12") (pinfunction "IOB1_12") (pintype "bidirectional"))
    )
    (net (code "102") (name "unconnected-(IC3A-IOB2-Pad11)") (class "Default")
      (node (ref "IC3") (pin "11") (pinfunction "IOB2_11") (pintype "bidirectional"))
    )
    (net (code "103") (name "unconnected-(IC3A-IOB3-Pad10)") (class "Default")
      (node (ref "IC3") (pin "10") (pinfunction "IOB3_10") (pintype "bidirectional"))
    )
    (net (code "104") (name "unconnected-(IC3A-IOB4-Pad9)") (class "Default")
      (node (ref "IC3") (pin "9") (pinfunction "IOB4_9") (pintype "bidirectional"))
    )
    (net (code "105") (name "unconnected-(IC3A-IOB5-Pad8)") (class "Default")
      (node (ref "IC3") (pin "8") (pinfunction "IOB5_8") (pintype "bidirectional"))
    )
    (net (code "106") (name "unconnected-(IC3A-IOB6-Pad7)") (class "Default")
      (node (ref "IC3") (pin "7") (pinfunction "IOB6_7") (pintype "bidirectional"))
    )
    (net (code "107") (name "unconnected-(IC3A-IOB7-Pad6)") (class "Default")
      (node (ref "IC3") (pin "6") (pinfunction "IOB7_6") (pintype "bidirectional"))
    )
    (net (code "108") (name "unconnected-(IC3A-TEST1-Pad39)") (class "Default")
      (node (ref "IC3") (pin "39") (pinfunction "TEST1_39") (pintype "input"))
    )
    (net (code "109") (name "unconnected-(IC3A-TEST2-Pad26)") (class "Default")
      (node (ref "IC3") (pin "26") (pinfunction "TEST2_26") (pintype "input"))
    )
    (net (code "110") (name "unconnected-(IC4A-IOA0-Pad21)") (class "Default")
      (node (ref "IC4") (pin "21") (pinfunction "IOA0_21") (pintype "bidirectional"))
    )
    (net (code "111") (name "unconnected-(IC4A-IOA1-Pad20)") (class "Default")
      (node (ref "IC4") (pin "20") (pinfunction "IOA1_20") (pintype "bidirectional"))
    )
    (net (code "112") (name "unconnected-(IC4A-IOA2-Pad19)") (class "Default")
      (node (ref "IC4") (pin "19") (pinfunction "IOA2_19") (pintype "bidirectional"))
    )
    (net (code "113") (name "unconnected-(IC4A-IOA3-Pad18)") (class "Default")
      (node (ref "IC4") (pin "18") (pinfunction "IOA3_18") (pintype "bidirectional"))
    )
    (net (code "114") (name "unconnected-(IC4A-IOA4-Pad17)") (class "Default")
      (node (ref "IC4") (pin "17") (pinfunction "IOA4_17") (pintype "bidirectional"))
    )
    (net (code "115") (name "unconnected-(IC4A-IOA5-Pad16)") (class "Default")
      (node (ref "IC4") (pin "16") (pinfunction "IOA5_16") (pintype "bidirectional"))
    )
    (net (code "116") (name "unconnected-(IC4A-IOA6-Pad15)") (class "Default")
      (node (ref "IC4") (pin "15") (pinfunction "IOA6_15") (pintype "bidirectional"))
    )
    (net (code "117") (name "unconnected-(IC4A-IOA7-Pad14)") (class "Default")
      (node (ref "IC4") (pin "14") (pinfunction "IOA7_14") (pintype "bidirectional"))
    )
    (net (code "118") (name "unconnected-(IC4A-IOB0-Pad13)") (class "Default")
      (node (ref "IC4") (pin "13") (pinfunction "IOB0_13") (pintype "bidirectional"))
    )
    (net (code "119") (name "unconnected-(IC4A-IOB1-Pad12)") (class "Default")
      (node (ref "IC4") (pin "12") (pinfunction "IOB1_12") (pintype "bidirectional"))
    )
    (net (code "120") (name "unconnected-(IC4A-IOB2-Pad11)") (class "Default")
      (node (ref "IC4") (pin "11") (pinfunction "IOB2_11") (pintype "bidirectional"))
    )
    (net (code "121") (name "unconnected-(IC4A-IOB3-Pad10)") (class "Default")
      (node (ref "IC4") (pin "10") (pinfunction "IOB3_10") (pintype "bidirectional"))
    )
    (net (code "122") (name "unconnected-(IC4A-IOB4-Pad9)") (class "Default")
      (node (ref "IC4") (pin "9") (pinfunction "IOB4_9") (pintype "bidirectional"))
    )
    (net (code "123") (name "unconnected-(IC4A-IOB5-Pad8)") (class "Default")
      (node (ref "IC4") (pin "8") (pinfunction "IOB5_8") (pintype "bidirectional"))
    )
    (net (code "124") (name "unconnected-(IC4A-IOB6-Pad7)") (class "Default")
      (node (ref "IC4") (pin "7") (pinfunction "IOB6_7") (pintype "bidirectional"))
    )
    (net (code "125") (name "unconnected-(IC4A-IOB7-Pad6)") (class "Default")
      (node (ref "IC4") (pin "6") (pinfunction "IOB7_6") (pintype "bidirectional"))
    )
    (net (code "126") (name "unconnected-(IC4A-TEST1-Pad39)") (class "Default")
      (node (ref "IC4") (pin "39") (pinfunction "TEST1_39") (pintype "input"))
    )
    (net (code "127") (name "unconnected-(IC4A-TEST2-Pad26)") (class "Default")
      (node (ref "IC4") (pin "26") (pinfunction "TEST2_26") (pintype "input"))
    )
    (net (code "128") (name "unconnected-(IC5A-IOA0-Pad21)") (class "Default")
      (node (ref "IC5") (pin "21") (pinfunction "IOA0_21") (pintype "bidirectional"))
    )
    (net (code "129") (name "unconnected-(IC5A-IOA1-Pad20)") (class "Default")
      (node (ref "IC5") (pin "20") (pinfunction "IOA1_20") (pintype "bidirectional"))
    )
    (net (code "130") (name "unconnected-(IC5A-IOA2-Pad19)") (class "Default")
      (node (ref "IC5") (pin "19") (pinfunction "IOA2_19") (pintype "bidirectional"))
    )
    (net (code "131") (name "unconnected-(IC5A-IOA3-Pad18)") (class "Default")
      (node (ref "IC5") (pin "18") (pinfunction "IOA3_18") (pintype "bidirectional"))
    )
    (net (code "132") (name "unconnected-(IC5A-IOA4-Pad17)") (class "Default")
      (node (ref "IC5") (pin "17") (pinfunction "IOA4_17") (pintype "bidirectional"))
    )
    (net (code "133") (name "unconnected-(IC5A-IOA5-Pad16)") (class "Default")
      (node (ref "IC5") (pin "16") (pinfunction "IOA5_16") (pintype "bidirectional"))
    )
    (net (code "134") (name "unconnected-(IC5A-IOA6-Pad15)") (class "Default")
      (node (ref "IC5") (pin "15") (pinfunction "IOA6_15") (pintype "bidirectional"))
    )
    (net (code "135") (name "unconnected-(IC5A-IOA7-Pad14)") (class "Default")
      (node (ref "IC5") (pin "14") (pinfunction "IOA7_14") (pintype "bidirectional"))
    )
    (net (code "136") (name "unconnected-(IC5A-IOB0-Pad13)") (class "Default")
      (node (ref "IC5") (pin "13") (pinfunction "IOB0_13") (pintype "bidirectional"))
    )
    (net (code "137") (name "unconnected-(IC5A-IOB1-Pad12)") (class "Default")
      (node (ref "IC5") (pin "12") (pinfunction "IOB1_12") (pintype "bidirectional"))
    )
    (net (code "138") (name "unconnected-(IC5A-IOB2-Pad11)") (class "Default")
      (node (ref "IC5") (pin "11") (pinfunction "IOB2_11") (pintype "bidirectional"))
    )
    (net (code "139") (name "unconnected-(IC5A-IOB3-Pad10)") (class "Default")
      (node (ref "IC5") (pin "10") (pinfunction "IOB3_10") (pintype "bidirectional"))
    )
    (net (code "140") (name "unconnected-(IC5A-IOB4-Pad9)") (class "Default")
      (node (ref "IC5") (pin "9") (pinfunction "IOB4_9") (pintype "bidirectional"))
    )
    (net (code "141") (name "unconnected-(IC5A-IOB5-Pad8)") (class "Default")
      (node (ref "IC5") (pin "8") (pinfunction "IOB5_8") (pintype "bidirectional"))
    )
    (net (code "142") (name "unconnected-(IC5A-IOB6-Pad7)") (class "Default")
      (node (ref "IC5") (pin "7") (pinfunction "IOB6_7") (pintype "bidirectional"))
    )
    (net (code "143") (name "unconnected-(IC5A-IOB7-Pad6)") (class "Default")
      (node (ref "IC5") (pin "6") (pinfunction "IOB7_6") (pintype "bidirectional"))
    )
    (net (code "144") (name "unconnected-(IC5A-TEST1-Pad39)") (class "Default")
      (node (ref "IC5") (pin "39") (pinfunction "TEST1_39") (pintype "input"))
    )
    (net (code "145") (name "unconnected-(IC5A-TEST2-Pad26)") (class "Default")
      (node (ref "IC5") (pin "26") (pinfunction "TEST2_26") (pintype "input"))
    )
    (net (code "146") (name "unconnected-(IC6A-Y1-Pad14)") (class "Default")
      (node (ref "IC6") (pin "14") (pinfunction "Y1_14") (pintype "output"))
    )
    (net (code "147") (name "unconnected-(IC6A-Y2-Pad13)") (class "Default")
      (node (ref "IC6") (pin "13") (pinfunction "Y2_13") (pintype "output"))
    )
    (net (code "148") (name "unconnected-(IC6A-Y3-Pad12)") (class "Default")
      (node (ref "IC6") (pin "12") (pinfunction "Y3_12") (pintype "output"))
    )
    (net (code "149") (name "unconnected-(IC6A-Y4-Pad11)") (class "Default")
      (node (ref "IC6") (pin "11") (pinfunction "Y4_11") (pintype "output"))
    )
    (net (code "150") (name "unconnected-(IC6A-Y5-Pad10)") (class "Default")
      (node (ref "IC6") (pin "10") (pinfunction "Y5_10") (pintype "output"))
    )
    (net (code "151") (name "unconnected-(IC6A-Y6-Pad9)") (class "Default")
      (node (ref "IC6") (pin "9") (pinfunction "Y6_9") (pintype "output"))
    )
    (net (code "152") (name "unconnected-(IC6A-Y7-Pad7)") (class "Default")
      (node (ref "IC6") (pin "7") (pinfunction "Y7_7") (pintype "output"))
    )
    (net (code "153") (name "unconnected-(IC8-BYPASS-Pad7)") (class "Default")
      (node (ref "IC8") (pin "7") (pinfunction "BYPASS_7") (pintype "passive"))
    )
    (net (code "154") (name "unconnected-(IC8-GAIN-Pad1)") (class "Default")
      (node (ref "IC8") (pin "1") (pinfunction "GAIN_1") (pintype "passive"))
    )
    (net (code "155") (name "unconnected-(IC8-GAIN-Pad8)") (class "Default")
      (node (ref "IC8") (pin "8") (pinfunction "GAIN_8") (pintype "passive"))
    )
    (net (code "156") (name "unconnected-(IC9-BYPASS-Pad7)") (class "Default")
      (node (ref "IC9") (pin "7") (pinfunction "BYPASS_7") (pintype "passive"))
    )
    (net (code "157") (name "unconnected-(IC9-GAIN-Pad1)") (class "Default")
      (node (ref "IC9") (pin "1") (pinfunction "GAIN_1") (pintype "passive"))
    )
    (net (code "158") (name "unconnected-(IC9-GAIN-Pad8)") (class "Default")
      (node (ref "IC9") (pin "8") (pinfunction "GAIN_8") (pintype "passive"))
    )
    (net (code "159") (name "unconnected-(X1B-Q-Pad7)") (class "Default")
      (node (ref "X1") (pin "7") (pinfunction "Q_7") (pintype "output"))
    )
    (net (code "160") (name "unconnected-(X1B-~{CART}-Pad8)") (class "Default")
      (node (ref "X1") (pin "8") (pinfunction "~{CART}_8") (pintype "open_collector"))
    )
    (net (code "161") (name "unconnected-(X1B-~{CTS}-Pad32)") (class "Default")
      (node (ref "X1") (pin "32") (pinfunction "~{CTS}_32") (pintype "output"))
    )
    (net (code "162") (name "unconnected-(X1B-~{HALT}-Pad3)") (class "Default")
      (node (ref "X1") (pin "3") (pinfunction "~{HALT}_3") (pintype "open_collector"))
    )
    (net (code "163") (name "unconnected-(X1B-~{NMI}-Pad4)") (class "Default")
      (node (ref "X1") (pin "4") (pinfunction "~{NMI}_4") (pintype "open_collector"))
    )
    (net (code "164") (name "unconnected-(X1B-~{SCS}-Pad36)") (class "Default")
      (node (ref "X1") (pin "36") (pinfunction "~{SCS}_36") (pintype "output"))
    )
    (net (code "165") (name "unconnected-(X1B-~{SLENB}-Pad40)") (class "Default")
      (node (ref "X1") (pin "40") (pinfunction "~{SLENB}_40") (pintype "open_collector"))
    )
    (net (code "166") (name "unconnected-(X2-Pad4)") (class "Default")
      (node (ref "X2") (pin "4") (pinfunction "4_4") (pintype "passive"))
    )
    (net (code "167") (name "unconnected-(X2-Pad5)") (class "Default")
      (node (ref "X2") (pin "5") (pinfunction "5_5") (pintype "passive"))
    )
  )
)
